# etherbotix.net
KiCad netlist of a schematic drawn in EAGLE
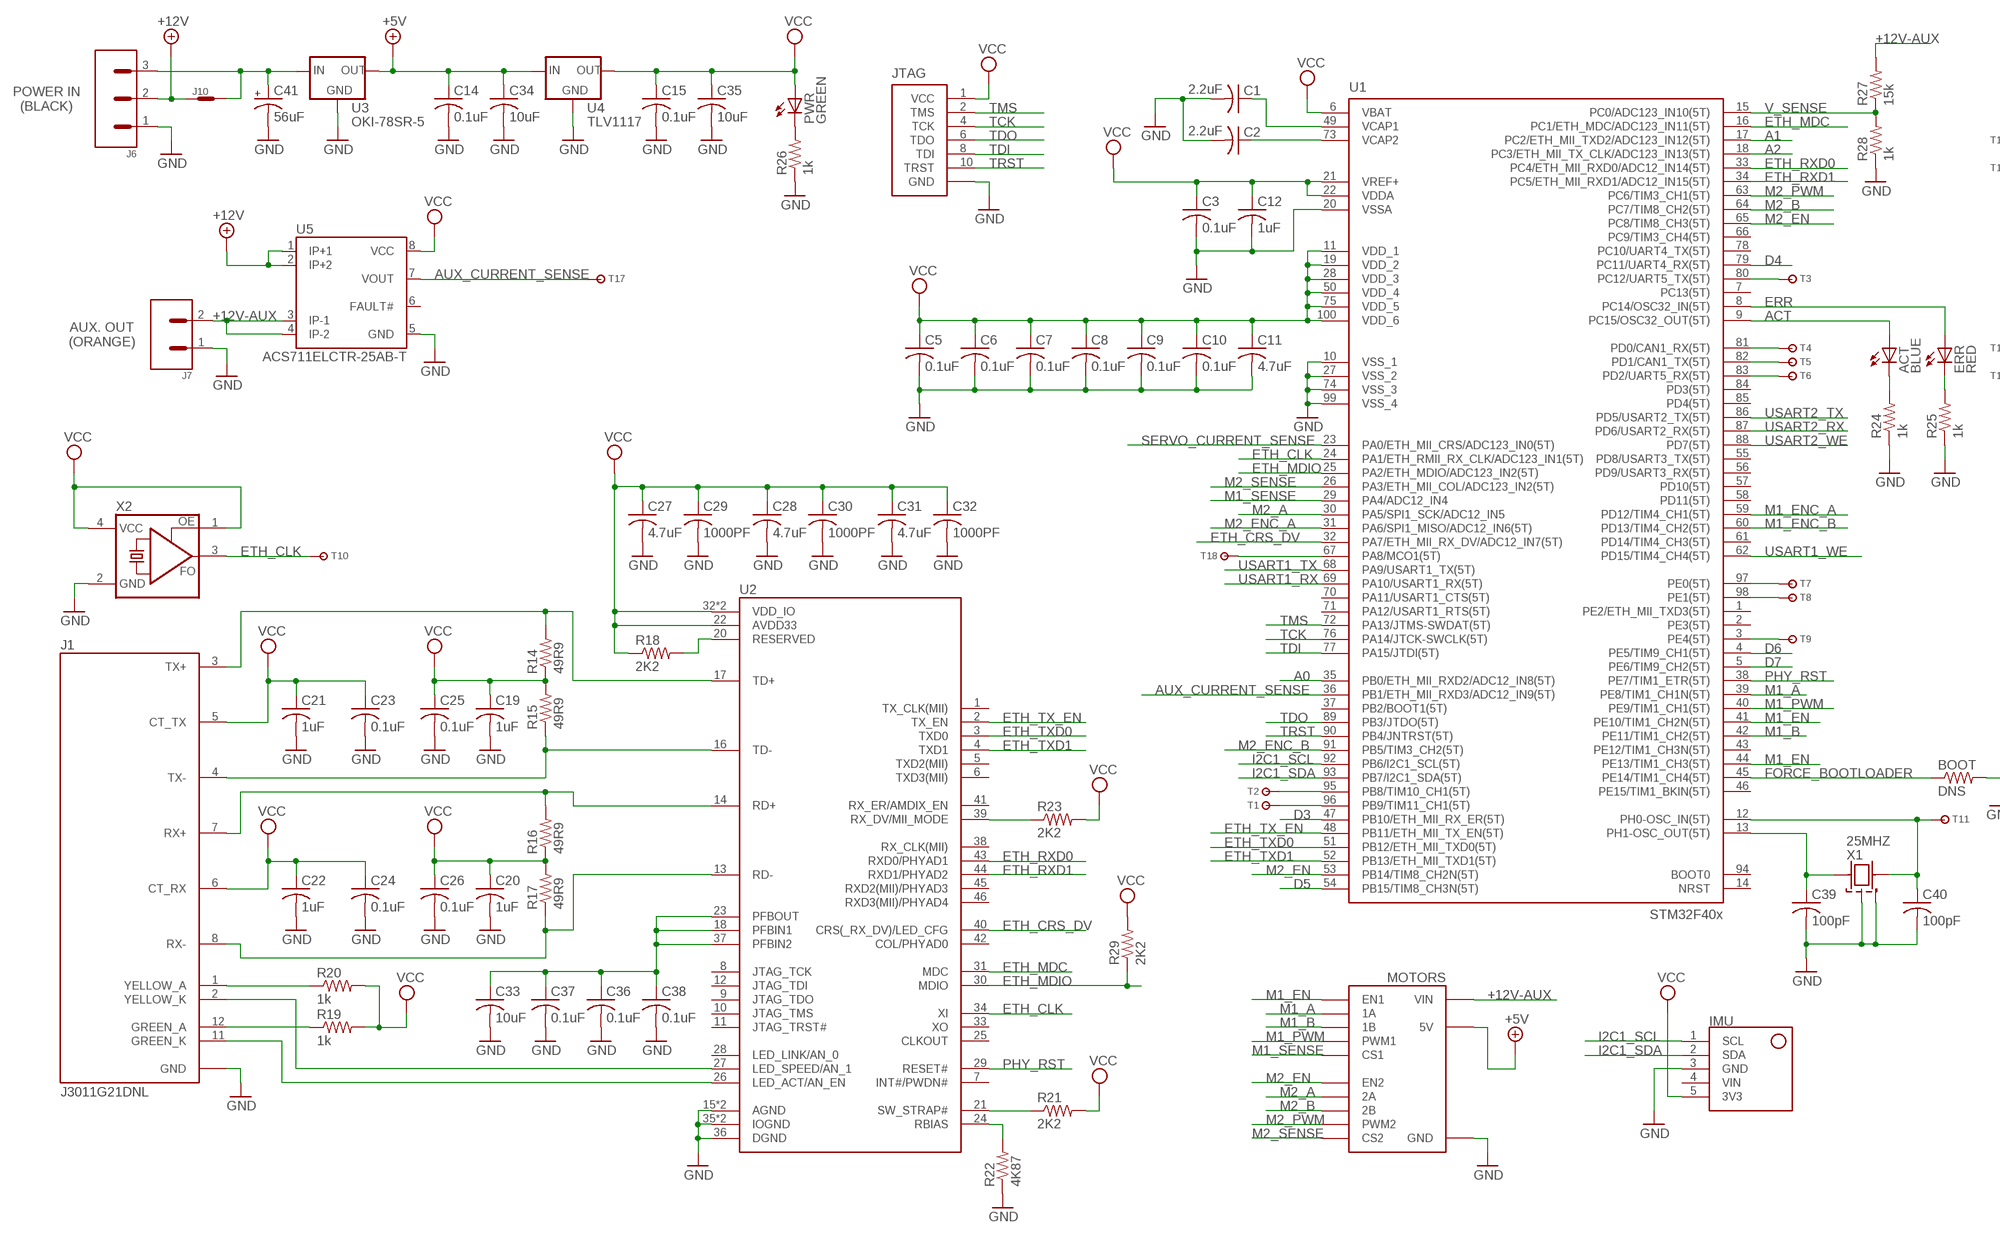
[diagram p0: schematic, sheet 1, part 1 of 2]
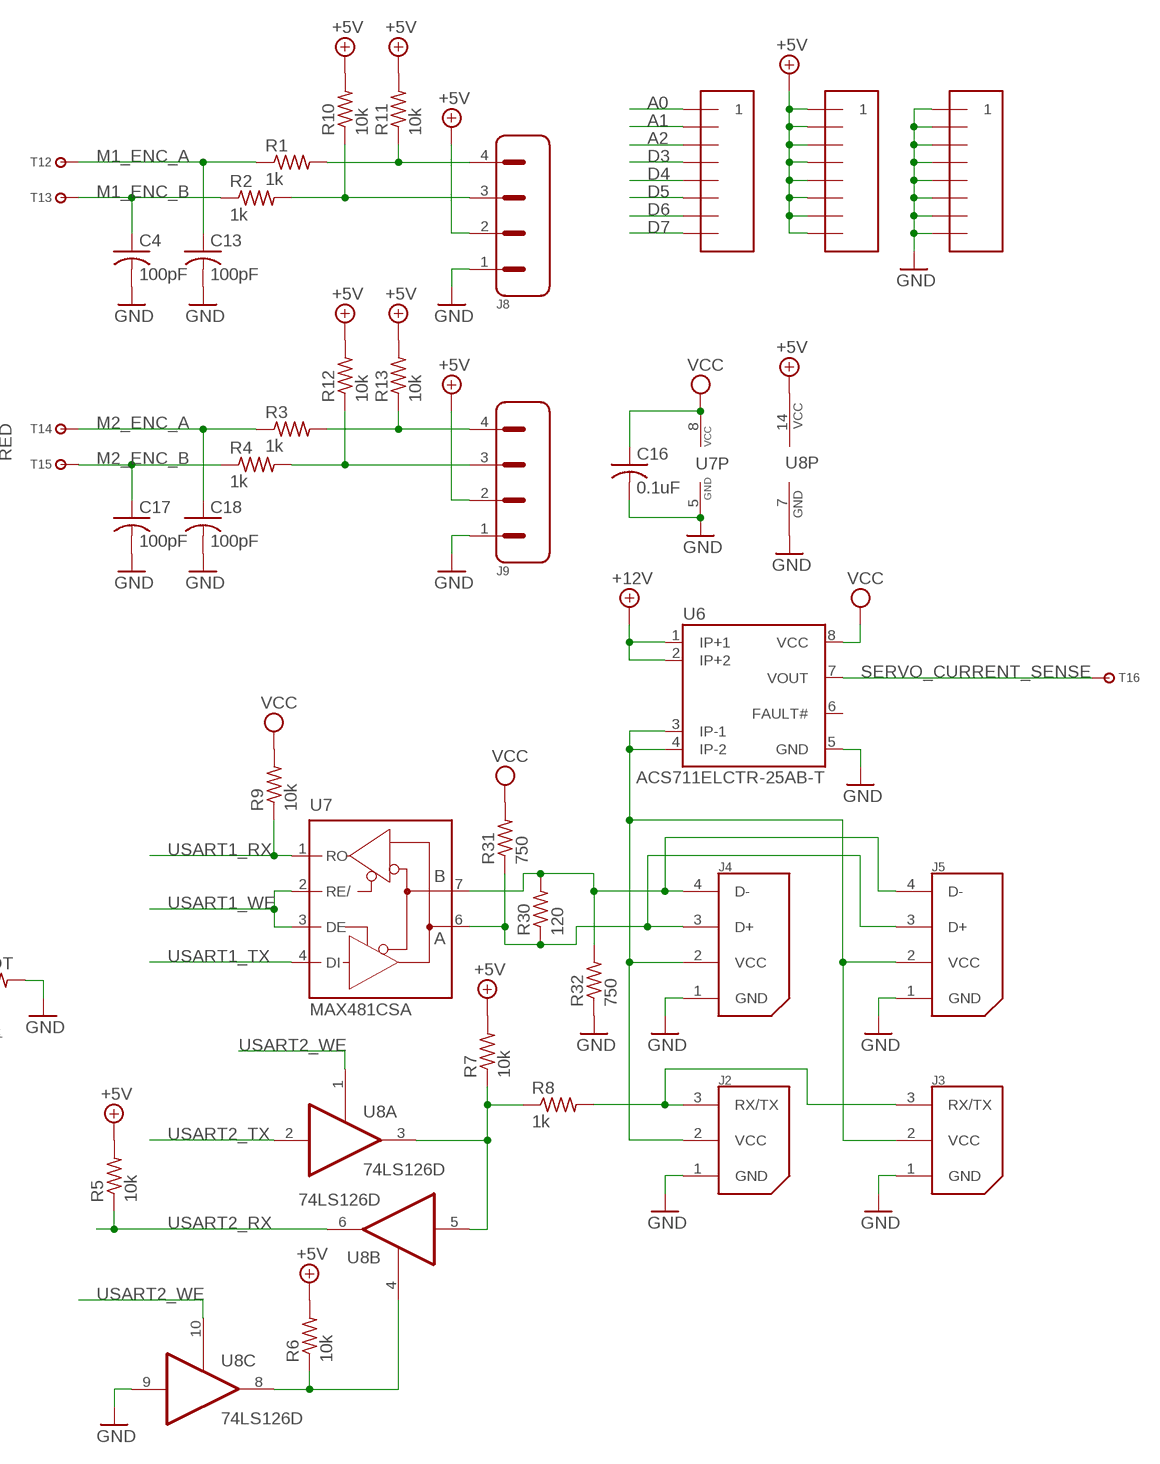
[diagram p1: schematic, sheet 1, part 2 of 2]

(export (version "E")
  (design (tool "Eeschema 10.0.6"))
  (components
    (comp (ref "ACT")
      (value "BLUE")
      (footprint "eagle-import:LED0603")
      (libsource (lib "eagle-import") (part "APT1608SGC"))
    )
    (comp (ref "BOOT")
      (value "DNS")
      (footprint "eagle-import:0603")
      (libsource (lib "eagle-import") (part "P1.00KHCT-ND"))
    )
    (comp (ref "C1")
      (value "2.2uF")
      (footprint "eagle-import:C0603")
      (libsource (lib "eagle-import") (part "C1608X5R1C225K"))
    )
    (comp (ref "C2")
      (value "2.2uF")
      (footprint "eagle-import:C0603")
      (libsource (lib "eagle-import") (part "C1608X5R1C225K"))
    )
    (comp (ref "C3")
      (value "0.1uF")
      (footprint "eagle-import:C0603")
      (libsource (lib "eagle-import") (part "C1608X7R1H104K"))
    )
    (comp (ref "C4")
      (value "100pF")
      (footprint "eagle-import:C0603")
      (libsource (lib "eagle-import") (part "C1608C0G1H101J"))
    )
    (comp (ref "C5")
      (value "0.1uF")
      (footprint "eagle-import:C0603")
      (libsource (lib "eagle-import") (part "C1608X7R1H104K"))
    )
    (comp (ref "C6")
      (value "0.1uF")
      (footprint "eagle-import:C0603")
      (libsource (lib "eagle-import") (part "C1608X7R1H104K"))
    )
    (comp (ref "C7")
      (value "0.1uF")
      (footprint "eagle-import:C0603")
      (libsource (lib "eagle-import") (part "C1608X7R1H104K"))
    )
    (comp (ref "C8")
      (value "0.1uF")
      (footprint "eagle-import:C0603")
      (libsource (lib "eagle-import") (part "C1608X7R1H104K"))
    )
    (comp (ref "C9")
      (value "0.1uF")
      (footprint "eagle-import:C0603")
      (libsource (lib "eagle-import") (part "C1608X7R1H104K"))
    )
    (comp (ref "C10")
      (value "0.1uF")
      (footprint "eagle-import:C0603")
      (libsource (lib "eagle-import") (part "C1608X7R1H104K"))
    )
    (comp (ref "C11")
      (value "4.7uF")
      (footprint "eagle-import:0603")
      (libsource (lib "eagle-import") (part "C1608X5R0J475K"))
    )
    (comp (ref "C12")
      (value "1uF")
      (footprint "eagle-import:C0603")
      (libsource (lib "eagle-import") (part "C1608X5R1H105M"))
    )
    (comp (ref "C13")
      (value "100pF")
      (footprint "eagle-import:C0603")
      (libsource (lib "eagle-import") (part "C1608C0G1H101J"))
    )
    (comp (ref "C14")
      (value "0.1uF")
      (footprint "eagle-import:C0603")
      (libsource (lib "eagle-import") (part "C1608X7R1H104K"))
    )
    (comp (ref "C15")
      (value "0.1uF")
      (footprint "eagle-import:C0603")
      (libsource (lib "eagle-import") (part "C1608X7R1H104K"))
    )
    (comp (ref "C16")
      (value "0.1uF")
      (footprint "eagle-import:C0603")
      (libsource (lib "eagle-import") (part "C1608X7R1H104K"))
    )
    (comp (ref "C17")
      (value "100pF")
      (footprint "eagle-import:C0603")
      (libsource (lib "eagle-import") (part "C1608C0G1H101J"))
    )
    (comp (ref "C18")
      (value "100pF")
      (footprint "eagle-import:C0603")
      (libsource (lib "eagle-import") (part "C1608C0G1H101J"))
    )
    (comp (ref "C19")
      (value "1uF")
      (footprint "eagle-import:C0603")
      (libsource (lib "eagle-import") (part "C1608X5R1H105M"))
    )
    (comp (ref "C20")
      (value "1uF")
      (footprint "eagle-import:C0603")
      (libsource (lib "eagle-import") (part "C1608X5R1H105M"))
    )
    (comp (ref "C21")
      (value "1uF")
      (footprint "eagle-import:C0603")
      (libsource (lib "eagle-import") (part "C1608X5R1H105M"))
    )
    (comp (ref "C22")
      (value "1uF")
      (footprint "eagle-import:C0603")
      (libsource (lib "eagle-import") (part "C1608X5R1H105M"))
    )
    (comp (ref "C23")
      (value "0.1uF")
      (footprint "eagle-import:C0603")
      (libsource (lib "eagle-import") (part "C1608X7R1H104K"))
    )
    (comp (ref "C24")
      (value "0.1uF")
      (footprint "eagle-import:C0603")
      (libsource (lib "eagle-import") (part "C1608X7R1H104K"))
    )
    (comp (ref "C25")
      (value "0.1uF")
      (footprint "eagle-import:C0603")
      (libsource (lib "eagle-import") (part "C1608X7R1H104K"))
    )
    (comp (ref "C26")
      (value "0.1uF")
      (footprint "eagle-import:C0603")
      (libsource (lib "eagle-import") (part "C1608X7R1H104K"))
    )
    (comp (ref "C27")
      (value "4.7uF")
      (footprint "eagle-import:0603")
      (libsource (lib "eagle-import") (part "C1608X5R0J475K"))
    )
    (comp (ref "C28")
      (value "4.7uF")
      (footprint "eagle-import:0603")
      (libsource (lib "eagle-import") (part "C1608X5R0J475K"))
    )
    (comp (ref "C29")
      (value "1000PF")
      (footprint "eagle-import:0603")
      (libsource (lib "eagle-import") (part "C1608X7R1H102K"))
    )
    (comp (ref "C30")
      (value "1000PF")
      (footprint "eagle-import:0603")
      (libsource (lib "eagle-import") (part "C1608X7R1H102K"))
    )
    (comp (ref "C31")
      (value "4.7uF")
      (footprint "eagle-import:0603")
      (libsource (lib "eagle-import") (part "C1608X5R0J475K"))
    )
    (comp (ref "C32")
      (value "1000PF")
      (footprint "eagle-import:0603")
      (libsource (lib "eagle-import") (part "C1608X7R1H102K"))
    )
    (comp (ref "C33")
      (value "10uF")
      (footprint "eagle-import:C0603")
      (libsource (lib "eagle-import") (part "C1608X5R0J106M"))
    )
    (comp (ref "C34")
      (value "10uF")
      (footprint "eagle-import:C0603")
      (libsource (lib "eagle-import") (part "C1608X5R0J106M"))
    )
    (comp (ref "C35")
      (value "10uF")
      (footprint "eagle-import:C0603")
      (libsource (lib "eagle-import") (part "C1608X5R0J106M"))
    )
    (comp (ref "C36")
      (value "0.1uF")
      (footprint "eagle-import:C0603")
      (libsource (lib "eagle-import") (part "C1608X7R1H104K"))
    )
    (comp (ref "C37")
      (value "0.1uF")
      (footprint "eagle-import:C0603")
      (libsource (lib "eagle-import") (part "C1608X7R1H104K"))
    )
    (comp (ref "C38")
      (value "0.1uF")
      (footprint "eagle-import:C0603")
      (libsource (lib "eagle-import") (part "C1608X7R1H104K"))
    )
    (comp (ref "C39")
      (value "100pF")
      (footprint "eagle-import:C0603")
      (libsource (lib "eagle-import") (part "C1608C0G1H101J"))
    )
    (comp (ref "C40")
      (value "100pF")
      (footprint "eagle-import:C0603")
      (libsource (lib "eagle-import") (part "C1608C0G1H101J"))
    )
    (comp (ref "C41")
      (value "56uF")
      (footprint "eagle-import:OSCON_SVPF_6.3MM")
      (libsource (lib "eagle-import") (part "25SVPF56M"))
    )
    (comp (ref "ERR")
      (value "RED")
      (footprint "eagle-import:LED0603")
      (libsource (lib "eagle-import") (part "APT1608SGC"))
    )
    (comp (ref "IMU")
      (value "MINI9IMU")
      (footprint "eagle-import:MINI9IMU")
      (libsource (lib "eagle-import") (part "MINI9IMU"))
    )
    (comp (ref "J1")
      (value "J3011G21DNL")
      (footprint "eagle-import:J3")
      (libsource (lib "eagle-import") (part "J3011G21DNL"))
    )
    (comp (ref "J2")
      (value "22-03-5035")
      (footprint "eagle-import:5267-3")
      (libsource (lib "eagle-import") (part "22-03-5035"))
    )
    (comp (ref "J3")
      (value "22-03-5035")
      (footprint "eagle-import:5267-3")
      (libsource (lib "eagle-import") (part "22-03-5035"))
    )
    (comp (ref "J4")
      (value "22-03-5045")
      (footprint "eagle-import:5267-4")
      (libsource (lib "eagle-import") (part "22-03-5045"))
    )
    (comp (ref "J5")
      (value "22-03-5045")
      (footprint "eagle-import:5267-4")
      (libsource (lib "eagle-import") (part "22-03-5045"))
    )
    (comp (ref "J6")
      (value "1760520000")
      (footprint "eagle-import:1760520000")
      (libsource (lib "eagle-import") (part "1760520000"))
    )
    (comp (ref "J7")
      (value "1760490000")
      (footprint "eagle-import:1760490000")
      (libsource (lib "eagle-import") (part "1760490000"))
    )
    (comp (ref "J8")
      (value "502443-0470")
      (footprint "eagle-import:502443-0470")
      (libsource (lib "eagle-import") (part "502443-0470"))
    )
    (comp (ref "J9")
      (value "502443-0470")
      (footprint "eagle-import:502443-0470")
      (libsource (lib "eagle-import") (part "502443-0470"))
    )
    (comp (ref "J10")
      (value "JUMPER")
      (footprint "eagle-import:J2")
      (libsource (lib "eagle-import") (part "JUMPER"))
    )
    (comp (ref "JTAG")
      (value "CORTEX_DEBUG-SHROUDED")
      (footprint "eagle-import:3220-10-0300-00")
      (libsource (lib "eagle-import") (part "CORTEX_DEBUG-SHROUDED"))
    )
    (comp (ref "MOTORS")
      (value "MD03A")
      (footprint "eagle-import:MD03A")
      (libsource (lib "eagle-import") (part "MD03A"))
    )
    (comp (ref "PWR")
      (value "GREEN")
      (footprint "eagle-import:LED0603")
      (libsource (lib "eagle-import") (part "APT1608SGC"))
    )
    (comp (ref "R1")
      (value "1k")
      (footprint "eagle-import:0603")
      (libsource (lib "eagle-import") (part "P1.00KHCT-ND"))
    )
    (comp (ref "R2")
      (value "1k")
      (footprint "eagle-import:0603")
      (libsource (lib "eagle-import") (part "P1.00KHCT-ND"))
    )
    (comp (ref "R3")
      (value "1k")
      (footprint "eagle-import:0603")
      (libsource (lib "eagle-import") (part "P1.00KHCT-ND"))
    )
    (comp (ref "R4")
      (value "1k")
      (footprint "eagle-import:0603")
      (libsource (lib "eagle-import") (part "P1.00KHCT-ND"))
    )
    (comp (ref "R5")
      (value "10k")
      (footprint "eagle-import:0603")
      (libsource (lib "eagle-import") (part "P10.0KHCT-ND"))
    )
    (comp (ref "R6")
      (value "10k")
      (footprint "eagle-import:0603")
      (libsource (lib "eagle-import") (part "P10.0KHCT-ND"))
    )
    (comp (ref "R7")
      (value "10k")
      (footprint "eagle-import:0603")
      (libsource (lib "eagle-import") (part "P10.0KHCT-ND"))
    )
    (comp (ref "R8")
      (value "1k")
      (footprint "eagle-import:0603")
      (libsource (lib "eagle-import") (part "P1.00KHCT-ND"))
    )
    (comp (ref "R9")
      (value "10k")
      (footprint "eagle-import:0603")
      (libsource (lib "eagle-import") (part "P10.0KHCT-ND"))
    )
    (comp (ref "R10")
      (value "10k")
      (footprint "eagle-import:0603")
      (libsource (lib "eagle-import") (part "P10.0KHCT-ND"))
    )
    (comp (ref "R11")
      (value "10k")
      (footprint "eagle-import:0603")
      (libsource (lib "eagle-import") (part "P10.0KHCT-ND"))
    )
    (comp (ref "R12")
      (value "10k")
      (footprint "eagle-import:0603")
      (libsource (lib "eagle-import") (part "P10.0KHCT-ND"))
    )
    (comp (ref "R13")
      (value "10k")
      (footprint "eagle-import:0603")
      (libsource (lib "eagle-import") (part "P10.0KHCT-ND"))
    )
    (comp (ref "R14")
      (value "49R9")
      (footprint "eagle-import:0603")
      (libsource (lib "eagle-import") (part "P49.9HCT-ND"))
    )
    (comp (ref "R15")
      (value "49R9")
      (footprint "eagle-import:0603")
      (libsource (lib "eagle-import") (part "P49.9HCT-ND"))
    )
    (comp (ref "R16")
      (value "49R9")
      (footprint "eagle-import:0603")
      (libsource (lib "eagle-import") (part "P49.9HCT-ND"))
    )
    (comp (ref "R17")
      (value "49R9")
      (footprint "eagle-import:0603")
      (libsource (lib "eagle-import") (part "P49.9HCT-ND"))
    )
    (comp (ref "R18")
      (value "2K2")
      (footprint "eagle-import:0603")
      (libsource (lib "eagle-import") (part "P2.20KHCT-ND"))
    )
    (comp (ref "R19")
      (value "1k")
      (footprint "eagle-import:0603")
      (libsource (lib "eagle-import") (part "P1.00KHCT-ND"))
    )
    (comp (ref "R20")
      (value "1k")
      (footprint "eagle-import:0603")
      (libsource (lib "eagle-import") (part "P1.00KHCT-ND"))
    )
    (comp (ref "R21")
      (value "2K2")
      (footprint "eagle-import:0603")
      (libsource (lib "eagle-import") (part "P2.20KHCT-ND"))
    )
    (comp (ref "R22")
      (value "4K87")
      (footprint "eagle-import:0603")
      (libsource (lib "eagle-import") (part "P4.87KHCT-ND"))
    )
    (comp (ref "R23")
      (value "2K2")
      (footprint "eagle-import:0603")
      (libsource (lib "eagle-import") (part "P2.20KHCT-ND"))
    )
    (comp (ref "R24")
      (value "1k")
      (footprint "eagle-import:0603")
      (libsource (lib "eagle-import") (part "P1.00KHCT-ND"))
    )
    (comp (ref "R25")
      (value "1k")
      (footprint "eagle-import:0603")
      (libsource (lib "eagle-import") (part "P1.00KHCT-ND"))
    )
    (comp (ref "R26")
      (value "1k")
      (footprint "eagle-import:0603")
      (libsource (lib "eagle-import") (part "P1.00KHCT-ND"))
    )
    (comp (ref "R27")
      (value "15k")
      (footprint "eagle-import:0603")
      (libsource (lib "eagle-import") (part "P15.0KHCT-ND"))
    )
    (comp (ref "R28")
      (value "1k")
      (footprint "eagle-import:0603")
      (libsource (lib "eagle-import") (part "P1.00KHCT-ND"))
    )
    (comp (ref "R29")
      (value "2K2")
      (footprint "eagle-import:0603")
      (libsource (lib "eagle-import") (part "P2.20KHCT-ND"))
    )
    (comp (ref "R30")
      (value "120")
      (footprint "eagle-import:0603")
      (libsource (lib "eagle-import") (part "P120HCT-ND"))
    )
    (comp (ref "R31")
      (value "750")
      (footprint "eagle-import:0603")
      (libsource (lib "eagle-import") (part "P750HCT-ND"))
    )
    (comp (ref "R32")
      (value "750")
      (footprint "eagle-import:0603")
      (libsource (lib "eagle-import") (part "P750HCT-ND"))
    )
    (comp (ref "T1")
      (value "TESTPAD")
      (footprint "eagle-import:TEST")
      (libsource (lib "eagle-import") (part "TESTPAD"))
    )
    (comp (ref "T2")
      (value "TESTPAD")
      (footprint "eagle-import:TEST")
      (libsource (lib "eagle-import") (part "TESTPAD"))
    )
    (comp (ref "T3")
      (value "TESTPAD")
      (footprint "eagle-import:TEST")
      (libsource (lib "eagle-import") (part "TESTPAD"))
    )
    (comp (ref "T4")
      (value "TESTPAD")
      (footprint "eagle-import:TEST")
      (libsource (lib "eagle-import") (part "TESTPAD"))
    )
    (comp (ref "T5")
      (value "TESTPAD")
      (footprint "eagle-import:TEST")
      (libsource (lib "eagle-import") (part "TESTPAD"))
    )
    (comp (ref "T6")
      (value "TESTPAD")
      (footprint "eagle-import:TEST")
      (libsource (lib "eagle-import") (part "TESTPAD"))
    )
    (comp (ref "T7")
      (value "TESTPAD")
      (footprint "eagle-import:TEST")
      (libsource (lib "eagle-import") (part "TESTPAD"))
    )
    (comp (ref "T8")
      (value "TESTPAD")
      (footprint "eagle-import:TEST")
      (libsource (lib "eagle-import") (part "TESTPAD"))
    )
    (comp (ref "T9")
      (value "TESTPAD")
      (footprint "eagle-import:TEST")
      (libsource (lib "eagle-import") (part "TESTPAD"))
    )
    (comp (ref "T10")
      (value "TESTPAD")
      (footprint "eagle-import:TEST")
      (libsource (lib "eagle-import") (part "TESTPAD"))
    )
    (comp (ref "T11")
      (value "TESTPAD")
      (footprint "eagle-import:TEST")
      (libsource (lib "eagle-import") (part "TESTPAD"))
    )
    (comp (ref "T12")
      (value "TESTPAD")
      (footprint "eagle-import:TEST")
      (libsource (lib "eagle-import") (part "TESTPAD"))
    )
    (comp (ref "T13")
      (value "TESTPAD")
      (footprint "eagle-import:TEST")
      (libsource (lib "eagle-import") (part "TESTPAD"))
    )
    (comp (ref "T14")
      (value "TESTPAD")
      (footprint "eagle-import:TEST")
      (libsource (lib "eagle-import") (part "TESTPAD"))
    )
    (comp (ref "T15")
      (value "TESTPAD")
      (footprint "eagle-import:TEST")
      (libsource (lib "eagle-import") (part "TESTPAD"))
    )
    (comp (ref "T16")
      (value "TESTPAD")
      (footprint "eagle-import:TEST")
      (libsource (lib "eagle-import") (part "TESTPAD"))
    )
    (comp (ref "T17")
      (value "TESTPAD")
      (footprint "eagle-import:TEST")
      (libsource (lib "eagle-import") (part "TESTPAD"))
    )
    (comp (ref "T18")
      (value "TESTPAD")
      (footprint "eagle-import:TEST")
      (libsource (lib "eagle-import") (part "TESTPAD"))
    )
    (comp (ref "U$1")
      (value "HEADER8")
      (footprint "eagle-import:1X8")
      (libsource (lib "eagle-import") (part "HEADER8"))
    )
    (comp (ref "U$2")
      (value "HEADER8")
      (footprint "eagle-import:1X8")
      (libsource (lib "eagle-import") (part "HEADER8"))
    )
    (comp (ref "U$3")
      (value "HEADER8")
      (footprint "eagle-import:1X8")
      (libsource (lib "eagle-import") (part "HEADER8"))
    )
    (comp (ref "U1")
      (value "STM32F407V")
      (footprint "eagle-import:TQFP100")
      (libsource (lib "eagle-import") (part "STM32F407V"))
    )
    (comp (ref "U2")
      (value "TLK110")
      (footprint "eagle-import:LQFP48")
      (libsource (lib "eagle-import") (part "TLK110"))
    )
    (comp (ref "U3")
      (value "OKI-78SR-5")
      (footprint "eagle-import:OKI-78SR")
      (fields (field (name "VOLTAGE") "5"))
      (libsource (lib "eagle-import") (part "OKI-78SR-W36-C-5/1.5"))
    )
    (comp (ref "U4")
      (value "TLV1117")
      (footprint "eagle-import:DPAK")
      (libsource (lib "eagle-import") (part "TLV1117-33IKVURG3KVU"))
    )
    (comp (ref "U5")
      (value "ACS711ELCTR-25AB-T")
      (footprint "eagle-import:SOIC8")
      (libsource (lib "eagle-import") (part "ACS711ELC?TR-25AB-T"))
    )
    (comp (ref "U6")
      (value "ACS711ELCTR-25AB-T")
      (footprint "eagle-import:SOIC8")
      (libsource (lib "eagle-import") (part "ACS711ELC?TR-25AB-T"))
    )
    (comp (ref "U7")
      (value "MAX481CSA")
      (footprint "eagle-import:SO08")
      (fields (field (name "MF") "MAXIM"))
      (libsource (lib "eagle-import") (part "MAX481CSA"))
    )
    (comp (ref "U8")
      (value "74LS126D")
      (footprint "eagle-import:SO14")
      (libsource (lib "eagle-import") (part "74126DLS"))
    )
    (comp (ref "X1")
      (value "25MHZ")
      (footprint "eagle-import:4LCC")
      (libsource (lib "eagle-import") (part "ABM3B-MHZ-B2-T25.000"))
    )
    (comp (ref "X2")
      (value "ASEMB-50.000MHZ-XY-T")
      (footprint "eagle-import:OSCILLATOR")
      (libsource (lib "eagle-import") (part "ASEMB-50.000MHZ-XY-T"))
    )
  )
  (nets
    (net (code "1") (name "+5V") (class "Default")
      (node (ref "C14") (pin "1") (pinfunction "1_1") (pintype "passive"))
      (node (ref "C34") (pin "1") (pinfunction "1_1") (pintype "passive"))
      (node (ref "J8") (pin "2") (pinfunction "2_2") (pintype "bidirectional"))
      (node (ref "J9") (pin "2") (pinfunction "2_2") (pintype "bidirectional"))
      (node (ref "MOTORS") (pin "5V") (pinfunction "5V_5V") (pintype "bidirectional"))
      (node (ref "R10") (pin "2") (pinfunction "2_2") (pintype "passive"))
      (node (ref "R11") (pin "2") (pinfunction "2_2") (pintype "passive"))
      (node (ref "R12") (pin "2") (pinfunction "2_2") (pintype "passive"))
      (node (ref "R13") (pin "2") (pinfunction "2_2") (pintype "passive"))
      (node (ref "R5") (pin "2") (pinfunction "2_2") (pintype "passive"))
      (node (ref "R6") (pin "2") (pinfunction "2_2") (pintype "passive"))
      (node (ref "R7") (pin "2") (pinfunction "2_2") (pintype "passive"))
      (node (ref "U$2") (pin "P$1") (pinfunction "1_P$1") (pintype "bidirectional"))
      (node (ref "U$2") (pin "P$2") (pinfunction "P$2_P$2") (pintype "bidirectional"))
      (node (ref "U$2") (pin "P$3") (pinfunction "P$3_P$3") (pintype "bidirectional"))
      (node (ref "U$2") (pin "P$4") (pinfunction "P$4_P$4") (pintype "bidirectional"))
      (node (ref "U$2") (pin "P$5") (pinfunction "P$5_P$5") (pintype "bidirectional"))
      (node (ref "U$2") (pin "P$6") (pinfunction "P$6_P$6") (pintype "bidirectional"))
      (node (ref "U$2") (pin "P$7") (pinfunction "P$7_P$7") (pintype "bidirectional"))
      (node (ref "U$2") (pin "P$8") (pinfunction "P$8_P$8") (pintype "bidirectional"))
      (node (ref "U3") (pin "P$3") (pinfunction "OUT_P$3") (pintype "passive"))
      (node (ref "U4") (pin "3") (pinfunction "IN_3") (pintype "input"))
      (node (ref "U8") (pin "14") (pinfunction "VCC_14") (pintype "power_in"))
    )
    (net (code "2") (name "+12V") (class "Default")
      (node (ref "J10") (pin "A") (pinfunction "A_A") (pintype "bidirectional"))
      (node (ref "J6") (pin "2") (pinfunction "2_2") (pintype "bidirectional"))
      (node (ref "U5") (pin "1") (pinfunction "IP+1_1") (pintype "bidirectional"))
      (node (ref "U5") (pin "2") (pinfunction "IP+2_2") (pintype "bidirectional"))
      (node (ref "U6") (pin "1") (pinfunction "IP+1_1") (pintype "bidirectional"))
      (node (ref "U6") (pin "2") (pinfunction "IP+2_2") (pintype "bidirectional"))
    )
    (net (code "3") (name "/+12V-AUX") (class "Default")
      (node (ref "J7") (pin "2") (pinfunction "2_2") (pintype "bidirectional"))
      (node (ref "MOTORS") (pin "VIN1") (pinfunction "VIN_VIN1") (pintype "bidirectional"))
      (node (ref "MOTORS") (pin "VIN2") (pinfunction "VIN_VIN2") (pintype "bidirectional"))
      (node (ref "R27") (pin "2") (pinfunction "2_2") (pintype "passive"))
      (node (ref "U5") (pin "3") (pinfunction "IP-1_3") (pintype "bidirectional"))
      (node (ref "U5") (pin "4") (pinfunction "IP-2_4") (pintype "bidirectional"))
    )
    (net (code "4") (name "/A0") (class "Default")
      (node (ref "U$1") (pin "P$1") (pinfunction "1_P$1") (pintype "bidirectional"))
      (node (ref "U1") (pin "35") (pinfunction "PB0/ETH_MII_RXD2/ADC12_IN8(5T)_35") (pintype "bidirectional"))
    )
    (net (code "5") (name "/A1") (class "Default")
      (node (ref "U$1") (pin "P$2") (pinfunction "P$2_P$2") (pintype "bidirectional"))
      (node (ref "U1") (pin "17") (pinfunction "PC2/ETH_MII_TXD2/ADC123_IN12(5T)_17") (pintype "bidirectional"))
    )
    (net (code "6") (name "/A2") (class "Default")
      (node (ref "U$1") (pin "P$3") (pinfunction "P$3_P$3") (pintype "bidirectional"))
      (node (ref "U1") (pin "18") (pinfunction "PC3/ETH_MII_TX_CLK/ADC123_IN13(5T)_18") (pintype "bidirectional"))
    )
    (net (code "7") (name "/ACT") (class "Default")
      (node (ref "ACT") (pin "A") (pinfunction "A_A") (pintype "passive"))
      (node (ref "U1") (pin "9") (pinfunction "PC15/OSC32_OUT(5T)_9") (pintype "bidirectional"))
    )
    (net (code "8") (name "/AUX_CURRENT_SENSE") (class "Default")
      (node (ref "T17") (pin "T") (pinfunction "1_T") (pintype "bidirectional"))
      (node (ref "U1") (pin "36") (pinfunction "PB1/ETH_MII_RXD3/ADC12_IN9(5T)_36") (pintype "bidirectional"))
      (node (ref "U5") (pin "7") (pinfunction "VOUT_7") (pintype "bidirectional"))
    )
    (net (code "9") (name "/D3") (class "Default")
      (node (ref "U$1") (pin "P$4") (pinfunction "P$4_P$4") (pintype "bidirectional"))
      (node (ref "U1") (pin "47") (pinfunction "PB10/ETH_MII_RX_ER(5T)_47") (pintype "bidirectional"))
    )
    (net (code "10") (name "/D4") (class "Default")
      (node (ref "U$1") (pin "P$5") (pinfunction "P$5_P$5") (pintype "bidirectional"))
      (node (ref "U1") (pin "79") (pinfunction "PC11/UART4_RX(5T)_79") (pintype "bidirectional"))
    )
    (net (code "11") (name "/D5") (class "Default")
      (node (ref "U$1") (pin "P$6") (pinfunction "P$6_P$6") (pintype "bidirectional"))
      (node (ref "U1") (pin "54") (pinfunction "PB15/TIM8_CH3N(5T)_54") (pintype "bidirectional"))
    )
    (net (code "12") (name "/D6") (class "Default")
      (node (ref "U$1") (pin "P$7") (pinfunction "P$7_P$7") (pintype "bidirectional"))
      (node (ref "U1") (pin "4") (pinfunction "PE5/TIM9_CH1(5T)_4") (pintype "bidirectional"))
    )
    (net (code "13") (name "/D7") (class "Default")
      (node (ref "U$1") (pin "P$8") (pinfunction "P$8_P$8") (pintype "bidirectional"))
      (node (ref "U1") (pin "5") (pinfunction "PE6/TIM9_CH2(5T)_5") (pintype "bidirectional"))
    )
    (net (code "14") (name "/ERR") (class "Default")
      (node (ref "ERR") (pin "A") (pinfunction "A_A") (pintype "passive"))
      (node (ref "U1") (pin "8") (pinfunction "PC14/OSC32_IN(5T)_8") (pintype "bidirectional"))
    )
    (net (code "15") (name "/ETH_CLK") (class "Default")
      (node (ref "T10") (pin "T") (pinfunction "1_T") (pintype "bidirectional"))
      (node (ref "U1") (pin "24") (pinfunction "PA1/ETH_RMII_RX_CLK/ADC123_IN1(5T)_24") (pintype "bidirectional"))
      (node (ref "U2") (pin "34") (pinfunction "XI_34") (pintype "bidirectional"))
      (node (ref "X2") (pin "3") (pinfunction "FO_3") (pintype "output"))
    )
    (net (code "16") (name "/ETH_CRS_DV") (class "Default")
      (node (ref "U1") (pin "32") (pinfunction "PA7/ETH_MII_RX_DV/ADC12_IN7(5T)_32") (pintype "bidirectional"))
      (node (ref "U2") (pin "40") (pinfunction "CRS(_RX_DV)/LED_CFG_40") (pintype "bidirectional"))
    )
    (net (code "17") (name "/ETH_MDC") (class "Default")
      (node (ref "U1") (pin "16") (pinfunction "PC1/ETH_MDC/ADC123_IN11(5T)_16") (pintype "bidirectional"))
      (node (ref "U2") (pin "31") (pinfunction "MDC_31") (pintype "bidirectional"))
    )
    (net (code "18") (name "/ETH_MDIO") (class "Default")
      (node (ref "R29") (pin "1") (pinfunction "1_1") (pintype "passive"))
      (node (ref "U1") (pin "25") (pinfunction "PA2/ETH_MDIO/ADC123_IN2(5T)_25") (pintype "bidirectional"))
      (node (ref "U2") (pin "30") (pinfunction "MDIO_30") (pintype "bidirectional"))
    )
    (net (code "19") (name "/ETH_RXD0") (class "Default")
      (node (ref "U1") (pin "33") (pinfunction "PC4/ETH_MII_RXD0/ADC12_IN14(5T)_33") (pintype "bidirectional"))
      (node (ref "U2") (pin "43") (pinfunction "RXD0/PHYAD1_43") (pintype "bidirectional"))
    )
    (net (code "20") (name "/ETH_RXD1") (class "Default")
      (node (ref "U1") (pin "34") (pinfunction "PC5/ETH_MII_RXD1/ADC12_IN15(5T)_34") (pintype "bidirectional"))
      (node (ref "U2") (pin "44") (pinfunction "RXD1/PHYAD2_44") (pintype "bidirectional"))
    )
    (net (code "21") (name "/ETH_TXD0") (class "Default")
      (node (ref "U1") (pin "51") (pinfunction "PB12/ETH_MII_TXD0(5T)_51") (pintype "bidirectional"))
      (node (ref "U2") (pin "3") (pinfunction "TXD0_3") (pintype "bidirectional"))
    )
    (net (code "22") (name "/ETH_TXD1") (class "Default")
      (node (ref "U1") (pin "52") (pinfunction "PB13/ETH_MII_TXD1(5T)_52") (pintype "bidirectional"))
      (node (ref "U2") (pin "4") (pinfunction "TXD1_4") (pintype "bidirectional"))
    )
    (net (code "23") (name "/ETH_TX_EN") (class "Default")
      (node (ref "U1") (pin "48") (pinfunction "PB11/ETH_MII_TX_EN(5T)_48") (pintype "bidirectional"))
      (node (ref "U2") (pin "2") (pinfunction "TX_EN_2") (pintype "bidirectional"))
    )
    (net (code "24") (name "/FORCE_BOOTLOADER") (class "Default")
      (node (ref "BOOT") (pin "1") (pinfunction "1_1") (pintype "passive"))
      (node (ref "U1") (pin "45") (pinfunction "PE14/TIM1_CH4(5T)_45") (pintype "bidirectional"))
    )
    (net (code "25") (name "/I2C1_SCL") (class "Default")
      (node (ref "IMU") (pin "1") (pinfunction "SCL_1") (pintype "bidirectional"))
      (node (ref "U1") (pin "92") (pinfunction "PB6/I2C1_SCL(5T)_92") (pintype "bidirectional"))
    )
    (net (code "26") (name "/I2C1_SDA") (class "Default")
      (node (ref "IMU") (pin "2") (pinfunction "SDA_2") (pintype "bidirectional"))
      (node (ref "U1") (pin "93") (pinfunction "PB7/I2C1_SDA(5T)_93") (pintype "bidirectional"))
    )
    (net (code "27") (name "/M1_A") (class "Default")
      (node (ref "MOTORS") (pin "1A") (pinfunction "1A_1A") (pintype "bidirectional"))
      (node (ref "U1") (pin "39") (pinfunction "PE8/TIM1_CH1N(5T)_39") (pintype "bidirectional"))
    )
    (net (code "28") (name "/M1_B") (class "Default")
      (node (ref "MOTORS") (pin "1B") (pinfunction "1B_1B") (pintype "bidirectional"))
      (node (ref "U1") (pin "42") (pinfunction "PE11/TIM1_CH2(5T)_42") (pintype "bidirectional"))
    )
    (net (code "29") (name "/M1_EN") (class "Default")
      (node (ref "MOTORS") (pin "EN1") (pinfunction "EN1_EN1") (pintype "bidirectional"))
      (node (ref "U1") (pin "41") (pinfunction "PE10/TIM1_CH2N(5T)_41") (pintype "bidirectional"))
      (node (ref "U1") (pin "44") (pinfunction "PE13/TIM1_CH3(5T)_44") (pintype "bidirectional"))
    )
    (net (code "30") (name "/M1_ENC_A") (class "Default")
      (node (ref "C13") (pin "1") (pinfunction "1_1") (pintype "passive"))
      (node (ref "R1") (pin "1") (pinfunction "1_1") (pintype "passive"))
      (node (ref "T12") (pin "T") (pinfunction "1_T") (pintype "bidirectional"))
      (node (ref "U1") (pin "59") (pinfunction "PD12/TIM4_CH1(5T)_59") (pintype "bidirectional"))
    )
    (net (code "31") (name "/M1_ENC_B") (class "Default")
      (node (ref "C4") (pin "1") (pinfunction "1_1") (pintype "passive"))
      (node (ref "R2") (pin "1") (pinfunction "1_1") (pintype "passive"))
      (node (ref "T13") (pin "T") (pinfunction "1_T") (pintype "bidirectional"))
      (node (ref "U1") (pin "60") (pinfunction "PD13/TIM4_CH2(5T)_60") (pintype "bidirectional"))
    )
    (net (code "32") (name "/M1_PWM") (class "Default")
      (node (ref "MOTORS") (pin "PWM1") (pinfunction "PWM1_PWM1") (pintype "bidirectional"))
      (node (ref "U1") (pin "40") (pinfunction "PE9/TIM1_CH1(5T)_40") (pintype "bidirectional"))
    )
    (net (code "33") (name "/M1_SENSE") (class "Default")
      (node (ref "MOTORS") (pin "CS1") (pinfunction "CS1_CS1") (pintype "bidirectional"))
      (node (ref "U1") (pin "29") (pinfunction "PA4/ADC12_IN4_29") (pintype "bidirectional"))
    )
    (net (code "34") (name "/M2_A") (class "Default")
      (node (ref "MOTORS") (pin "2A") (pinfunction "2A_2A") (pintype "bidirectional"))
      (node (ref "U1") (pin "30") (pinfunction "PA5/SPI1_SCK/ADC12_IN5_30") (pintype "bidirectional"))
    )
    (net (code "35") (name "/M2_B") (class "Default")
      (node (ref "MOTORS") (pin "2B") (pinfunction "2B_2B") (pintype "bidirectional"))
      (node (ref "U1") (pin "64") (pinfunction "PC7/TIM8_CH2(5T)_64") (pintype "bidirectional"))
    )
    (net (code "36") (name "/M2_EN") (class "Default")
      (node (ref "MOTORS") (pin "EN2") (pinfunction "EN2_EN2") (pintype "bidirectional"))
      (node (ref "U1") (pin "53") (pinfunction "PB14/TIM8_CH2N(5T)_53") (pintype "bidirectional"))
      (node (ref "U1") (pin "65") (pinfunction "PC8/TIM8_CH3(5T)_65") (pintype "bidirectional"))
    )
    (net (code "37") (name "/M2_ENC_A") (class "Default")
      (node (ref "C18") (pin "1") (pinfunction "1_1") (pintype "passive"))
      (node (ref "R3") (pin "1") (pinfunction "1_1") (pintype "passive"))
      (node (ref "T14") (pin "T") (pinfunction "1_T") (pintype "bidirectional"))
      (node (ref "U1") (pin "31") (pinfunction "PA6/SPI1_MISO/ADC12_IN6(5T)_31") (pintype "bidirectional"))
    )
    (net (code "38") (name "/M2_ENC_B") (class "Default")
      (node (ref "C17") (pin "1") (pinfunction "1_1") (pintype "passive"))
      (node (ref "R4") (pin "1") (pinfunction "1_1") (pintype "passive"))
      (node (ref "T15") (pin "T") (pinfunction "1_T") (pintype "bidirectional"))
      (node (ref "U1") (pin "91") (pinfunction "PB5/TIM3_CH2(5T)_91") (pintype "bidirectional"))
    )
    (net (code "39") (name "/M2_PWM") (class "Default")
      (node (ref "MOTORS") (pin "PWM2") (pinfunction "PWM2_PWM2") (pintype "bidirectional"))
      (node (ref "U1") (pin "63") (pinfunction "PC6/TIM3_CH1(5T)_63") (pintype "bidirectional"))
    )
    (net (code "40") (name "/M2_SENSE") (class "Default")
      (node (ref "MOTORS") (pin "CS2") (pinfunction "CS2_CS2") (pintype "bidirectional"))
      (node (ref "U1") (pin "26") (pinfunction "PA3/ETH_MII_COL/ADC123_IN2(5T)_26") (pintype "bidirectional"))
    )
    (net (code "41") (name "/PHY_RST") (class "Default")
      (node (ref "U1") (pin "38") (pinfunction "PE7/TIM1_ETR(5T)_38") (pintype "bidirectional"))
      (node (ref "U2") (pin "29") (pinfunction "RESET#_29") (pintype "bidirectional"))
    )
    (net (code "42") (name "/SERVO_CURRENT_SENSE") (class "Default")
      (node (ref "T16") (pin "T") (pinfunction "1_T") (pintype "bidirectional"))
      (node (ref "U1") (pin "23") (pinfunction "PA0/ETH_MII_CRS/ADC123_IN0(5T)_23") (pintype "bidirectional"))
      (node (ref "U6") (pin "7") (pinfunction "VOUT_7") (pintype "bidirectional"))
    )
    (net (code "43") (name "/TCK") (class "Default")
      (node (ref "JTAG") (pin "4") (pinfunction "TCK_4") (pintype "bidirectional"))
      (node (ref "U1") (pin "76") (pinfunction "PA14/JTCK-SWCLK(5T)_76") (pintype "bidirectional"))
    )
    (net (code "44") (name "/TDI") (class "Default")
      (node (ref "JTAG") (pin "8") (pinfunction "TDI_8") (pintype "bidirectional"))
      (node (ref "U1") (pin "77") (pinfunction "PA15/JTDI(5T)_77") (pintype "bidirectional"))
    )
    (net (code "45") (name "/TDO") (class "Default")
      (node (ref "JTAG") (pin "6") (pinfunction "TDO_6") (pintype "bidirectional"))
      (node (ref "U1") (pin "89") (pinfunction "PB3/JTDO(5T)_89") (pintype "bidirectional"))
    )
    (net (code "46") (name "/TMS") (class "Default")
      (node (ref "JTAG") (pin "2") (pinfunction "TMS_2") (pintype "bidirectional"))
      (node (ref "U1") (pin "72") (pinfunction "PA13/JTMS-SWDAT(5T)_72") (pintype "bidirectional"))
    )
    (net (code "47") (name "/TRST") (class "Default")
      (node (ref "JTAG") (pin "10") (pinfunction "TRST_10") (pintype "bidirectional"))
      (node (ref "U1") (pin "90") (pinfunction "PB4/JNTRST(5T)_90") (pintype "bidirectional"))
    )
    (net (code "48") (name "/USART1_RX") (class "Default")
      (node (ref "R9") (pin "1") (pinfunction "1_1") (pintype "passive"))
      (node (ref "U1") (pin "69") (pinfunction "PA10/USART1_RX(5T)_69") (pintype "bidirectional"))
      (node (ref "U7") (pin "1") (pinfunction "RO_1") (pintype "output"))
    )
    (net (code "49") (name "/USART1_TX") (class "Default")
      (node (ref "U1") (pin "68") (pinfunction "PA9/USART1_TX(5T)_68") (pintype "bidirectional"))
      (node (ref "U7") (pin "4") (pinfunction "DI_4") (pintype "input"))
    )
    (net (code "50") (name "/USART1_WE") (class "Default")
      (node (ref "U1") (pin "62") (pinfunction "PD15/TIM4_CH4(5T)_62") (pintype "bidirectional"))
      (node (ref "U7") (pin "2") (pinfunction "RE/_2") (pintype "input"))
      (node (ref "U7") (pin "3") (pinfunction "DE_3") (pintype "input"))
    )
    (net (code "51") (name "/USART2_RX") (class "Default")
      (node (ref "R5") (pin "1") (pinfunction "1_1") (pintype "passive"))
      (node (ref "U1") (pin "87") (pinfunction "PD6/USART2_RX(5T)_87") (pintype "bidirectional"))
      (node (ref "U8") (pin "6") (pinfunction "O_6") (pintype "output"))
    )
    (net (code "52") (name "/USART2_TX") (class "Default")
      (node (ref "U1") (pin "86") (pinfunction "PD5/USART2_TX(5T)_86") (pintype "bidirectional"))
      (node (ref "U8") (pin "2") (pinfunction "I_2") (pintype "input"))
    )
    (net (code "53") (name "/USART2_WE") (class "Default")
      (node (ref "U1") (pin "88") (pinfunction "PD7(5T)_88") (pintype "bidirectional"))
      (node (ref "U8") (pin "1") (pinfunction "OE_1") (pintype "input"))
      (node (ref "U8") (pin "10") (pinfunction "OE_10") (pintype "input"))
    )
    (net (code "54") (name "/V_SENSE") (class "Default")
      (node (ref "R27") (pin "1") (pinfunction "1_1") (pintype "passive"))
      (node (ref "R28") (pin "2") (pinfunction "2_2") (pintype "passive"))
      (node (ref "U1") (pin "15") (pinfunction "PC0/ADC123_IN10(5T)_15") (pintype "bidirectional"))
    )
    (net (code "55") (name "GND") (class "Default")
      (node (ref "BOOT") (pin "2") (pinfunction "2_2") (pintype "passive"))
      (node (ref "C1") (pin "2") (pinfunction "2_2") (pintype "passive"))
      (node (ref "C10") (pin "2") (pinfunction "2_2") (pintype "passive"))
      (node (ref "C11") (pin "2") (pinfunction "2_2") (pintype "passive"))
      (node (ref "C12") (pin "2") (pinfunction "2_2") (pintype "passive"))
      (node (ref "C13") (pin "2") (pinfunction "2_2") (pintype "passive"))
      (node (ref "C14") (pin "2") (pinfunction "2_2") (pintype "passive"))
      (node (ref "C15") (pin "2") (pinfunction "2_2") (pintype "passive"))
      (node (ref "C16") (pin "2") (pinfunction "2_2") (pintype "passive"))
      (node (ref "C17") (pin "2") (pinfunction "2_2") (pintype "passive"))
      (node (ref "C18") (pin "2") (pinfunction "2_2") (pintype "passive"))
      (node (ref "C19") (pin "2") (pinfunction "2_2") (pintype "passive"))
      (node (ref "C2") (pin "2") (pinfunction "2_2") (pintype "passive"))
      (node (ref "C20") (pin "2") (pinfunction "2_2") (pintype "passive"))
      (node (ref "C21") (pin "2") (pinfunction "2_2") (pintype "passive"))
      (node (ref "C22") (pin "2") (pinfunction "2_2") (pintype "passive"))
      (node (ref "C23") (pin "2") (pinfunction "2_2") (pintype "passive"))
      (node (ref "C24") (pin "2") (pinfunction "2_2") (pintype "passive"))
      (node (ref "C25") (pin "2") (pinfunction "2_2") (pintype "passive"))
      (node (ref "C26") (pin "2") (pinfunction "2_2") (pintype "passive"))
      (node (ref "C27") (pin "2") (pinfunction "2_2") (pintype "passive"))
      (node (ref "C28") (pin "2") (pinfunction "2_2") (pintype "passive"))
      (node (ref "C29") (pin "2") (pinfunction "2_2") (pintype "passive"))
      (node (ref "C3") (pin "2") (pinfunction "2_2") (pintype "passive"))
      (node (ref "C30") (pin "2") (pinfunction "2_2") (pintype "passive"))
      (node (ref "C31") (pin "2") (pinfunction "2_2") (pintype "passive"))
      (node (ref "C32") (pin "2") (pinfunction "2_2") (pintype "passive"))
      (node (ref "C33") (pin "2") (pinfunction "2_2") (pintype "passive"))
      (node (ref "C34") (pin "2") (pinfunction "2_2") (pintype "passive"))
      (node (ref "C35") (pin "2") (pinfunction "2_2") (pintype "passive"))
      (node (ref "C36") (pin "2") (pinfunction "2_2") (pintype "passive"))
      (node (ref "C37") (pin "2") (pinfunction "2_2") (pintype "passive"))
      (node (ref "C38") (pin "2") (pinfunction "2_2") (pintype "passive"))
      (node (ref "C39") (pin "2") (pinfunction "2_2") (pintype "passive"))
      (node (ref "C4") (pin "2") (pinfunction "2_2") (pintype "passive"))
      (node (ref "C40") (pin "2") (pinfunction "2_2") (pintype "passive"))
      (node (ref "C41") (pin "-") (pinfunction "-_-") (pintype "passive"))
      (node (ref "C5") (pin "2") (pinfunction "2_2") (pintype "passive"))
      (node (ref "C6") (pin "2") (pinfunction "2_2") (pintype "passive"))
      (node (ref "C7") (pin "2") (pinfunction "2_2") (pintype "passive"))
      (node (ref "C8") (pin "2") (pinfunction "2_2") (pintype "passive"))
      (node (ref "C9") (pin "2") (pinfunction "2_2") (pintype "passive"))
      (node (ref "IMU") (pin "3") (pinfunction "GND_3") (pintype "bidirectional"))
      (node (ref "J1") (pin "10") (pinfunction "GND_10") (pintype "bidirectional"))
      (node (ref "J1") (pin "9") (pinfunction "GND_9") (pintype "bidirectional"))
      (node (ref "J1") (pin "A") (pinfunction "GND_A") (pintype "bidirectional"))
      (node (ref "J1") (pin "B") (pinfunction "GND_B") (pintype "bidirectional"))
      (node (ref "J2") (pin "1") (pinfunction "GND_1") (pintype "bidirectional"))
      (node (ref "J3") (pin "1") (pinfunction "GND_1") (pintype "bidirectional"))
      (node (ref "J4") (pin "1") (pinfunction "GND_1") (pintype "bidirectional"))
      (node (ref "J5") (pin "1") (pinfunction "GND_1") (pintype "bidirectional"))
      (node (ref "J6") (pin "1") (pinfunction "1_1") (pintype "bidirectional"))
      (node (ref "J7") (pin "1") (pinfunction "1_1") (pintype "bidirectional"))
      (node (ref "J8") (pin "1") (pinfunction "1_1") (pintype "bidirectional"))
      (node (ref "J9") (pin "1") (pinfunction "1_1") (pintype "bidirectional"))
      (node (ref "JTAG") (pin "3") (pinfunction "GND_3") (pintype "bidirectional"))
      (node (ref "JTAG") (pin "5") (pinfunction "GND_5") (pintype "bidirectional"))
      (node (ref "JTAG") (pin "9") (pinfunction "GND_9") (pintype "bidirectional"))
      (node (ref "MOTORS") (pin "GND1") (pinfunction "GND_GND1") (pintype "bidirectional"))
      (node (ref "MOTORS") (pin "GND2") (pinfunction "GND_GND2") (pintype "bidirectional"))
      (node (ref "R22") (pin "1") (pinfunction "1_1") (pintype "passive"))
      (node (ref "R24") (pin "1") (pinfunction "1_1") (pintype "passive"))
      (node (ref "R25") (pin "1") (pinfunction "1_1") (pintype "passive"))
      (node (ref "R26") (pin "1") (pinfunction "1_1") (pintype "passive"))
      (node (ref "R28") (pin "1") (pinfunction "1_1") (pintype "passive"))
      (node (ref "R32") (pin "1") (pinfunction "1_1") (pintype "passive"))
      (node (ref "U$3") (pin "P$1") (pinfunction "1_P$1") (pintype "bidirectional"))
      (node (ref "U$3") (pin "P$2") (pinfunction "P$2_P$2") (pintype "bidirectional"))
      (node (ref "U$3") (pin "P$3") (pinfunction "P$3_P$3") (pintype "bidirectional"))
      (node (ref "U$3") (pin "P$4") (pinfunction "P$4_P$4") (pintype "bidirectional"))
      (node (ref "U$3") (pin "P$5") (pinfunction "P$5_P$5") (pintype "bidirectional"))
      (node (ref "U$3") (pin "P$6") (pinfunction "P$6_P$6") (pintype "bidirectional"))
      (node (ref "U$3") (pin "P$7") (pinfunction "P$7_P$7") (pintype "bidirectional"))
      (node (ref "U$3") (pin "P$8") (pinfunction "P$8_P$8") (pintype "bidirectional"))
      (node (ref "U1") (pin "10") (pinfunction "VSS_1_10") (pintype "bidirectional"))
      (node (ref "U1") (pin "20") (pinfunction "VSSA_20") (pintype "bidirectional"))
      (node (ref "U1") (pin "27") (pinfunction "VSS_2_27") (pintype "bidirectional"))
      (node (ref "U1") (pin "74") (pinfunction "VSS_3_74") (pintype "bidirectional"))
      (node (ref "U1") (pin "99") (pinfunction "VSS_4_99") (pintype "bidirectional"))
      (node (ref "U2") (pin "15") (pinfunction "AGND_15") (pintype "bidirectional"))
      (node (ref "U2") (pin "19") (pinfunction "AGND_19") (pintype "bidirectional"))
      (node (ref "U2") (pin "35") (pinfunction "IOGND_35") (pintype "bidirectional"))
      (node (ref "U2") (pin "36") (pinfunction "DGND_36") (pintype "bidirectional"))
      (node (ref "U2") (pin "47") (pinfunction "IOGND_47") (pintype "bidirectional"))
      (node (ref "U3") (pin "P$2") (pinfunction "GND_P$2") (pintype "input"))
      (node (ref "U4") (pin "1") (pinfunction "GND_1") (pintype "input"))
      (node (ref "U5") (pin "5") (pinfunction "GND_5") (pintype "bidirectional"))
      (node (ref "U6") (pin "5") (pinfunction "GND_5") (pintype "bidirectional"))
      (node (ref "U7") (pin "5") (pinfunction "GND_5") (pintype "power_in"))
      (node (ref "U8") (pin "7") (pinfunction "GND_7") (pintype "power_in"))
      (node (ref "U8") (pin "9") (pinfunction "I_9") (pintype "input"))
      (node (ref "X1") (pin "2") (pinfunction "G1_2") (pintype "bidirectional"))
      (node (ref "X1") (pin "4") (pinfunction "G2_4") (pintype "bidirectional"))
      (node (ref "X2") (pin "2") (pinfunction "GND_2") (pintype "power_in"))
    )
    (net (code "56") (name "Net-(ACT-PadC)") (class "Default")
      (node (ref "ACT") (pin "C") (pinfunction "C_C") (pintype "passive"))
      (node (ref "R24") (pin "2") (pinfunction "2_2") (pintype "passive"))
    )
    (net (code "57") (name "Net-(ERR-PadC)") (class "Default")
      (node (ref "ERR") (pin "C") (pinfunction "C_C") (pintype "passive"))
      (node (ref "R25") (pin "2") (pinfunction "2_2") (pintype "passive"))
    )
    (net (code "58") (name "Net-(J1-GREEN_A)") (class "Default")
      (node (ref "J1") (pin "12") (pinfunction "GREEN_A_12") (pintype "bidirectional"))
      (node (ref "R19") (pin "1") (pinfunction "1_1") (pintype "passive"))
    )
    (net (code "59") (name "Net-(J1-GREEN_K)") (class "Default")
      (node (ref "J1") (pin "11") (pinfunction "GREEN_K_11") (pintype "bidirectional"))
      (node (ref "U2") (pin "26") (pinfunction "LED_ACT/AN_EN_26") (pintype "bidirectional"))
    )
    (net (code "60") (name "Net-(J1-RX+)") (class "Default")
      (node (ref "J1") (pin "7") (pinfunction "RX+_7") (pintype "bidirectional"))
      (node (ref "R16") (pin "2") (pinfunction "2_2") (pintype "passive"))
      (node (ref "U2") (pin "14") (pinfunction "RD+_14") (pintype "bidirectional"))
    )
    (net (code "61") (name "Net-(J1-RX-)") (class "Default")
      (node (ref "J1") (pin "8") (pinfunction "RX-_8") (pintype "bidirectional"))
      (node (ref "R17") (pin "1") (pinfunction "1_1") (pintype "passive"))
      (node (ref "U2") (pin "13") (pinfunction "RD-_13") (pintype "bidirectional"))
    )
    (net (code "62") (name "Net-(J1-TX+)") (class "Default")
      (node (ref "J1") (pin "3") (pinfunction "TX+_3") (pintype "bidirectional"))
      (node (ref "R14") (pin "2") (pinfunction "2_2") (pintype "passive"))
      (node (ref "U2") (pin "17") (pinfunction "TD+_17") (pintype "bidirectional"))
    )
    (net (code "63") (name "Net-(J1-TX-)") (class "Default")
      (node (ref "J1") (pin "4") (pinfunction "TX-_4") (pintype "bidirectional"))
      (node (ref "R15") (pin "1") (pinfunction "1_1") (pintype "passive"))
      (node (ref "U2") (pin "16") (pinfunction "TD-_16") (pintype "bidirectional"))
    )
    (net (code "64") (name "Net-(J1-YELLOW_A)") (class "Default")
      (node (ref "J1") (pin "1") (pinfunction "YELLOW_A_1") (pintype "bidirectional"))
      (node (ref "R20") (pin "1") (pinfunction "1_1") (pintype "passive"))
    )
    (net (code "65") (name "Net-(J1-YELLOW_K)") (class "Default")
      (node (ref "J1") (pin "2") (pinfunction "YELLOW_K_2") (pintype "bidirectional"))
      (node (ref "U2") (pin "27") (pinfunction "LED_SPEED/AN_1_27") (pintype "bidirectional"))
    )
    (net (code "66") (name "Net-(J2-RX{slash}TX)") (class "Default")
      (node (ref "J2") (pin "3") (pinfunction "RX/TX_3") (pintype "bidirectional"))
      (node (ref "J3") (pin "3") (pinfunction "RX/TX_3") (pintype "bidirectional"))
      (node (ref "R8") (pin "2") (pinfunction "2_2") (pintype "passive"))
    )
    (net (code "67") (name "Net-(J2-VCC)") (class "Default")
      (node (ref "J2") (pin "2") (pinfunction "VCC_2") (pintype "bidirectional"))
      (node (ref "J3") (pin "2") (pinfunction "VCC_2") (pintype "bidirectional"))
      (node (ref "J4") (pin "2") (pinfunction "VCC_2") (pintype "bidirectional"))
      (node (ref "J5") (pin "2") (pinfunction "VCC_2") (pintype "bidirectional"))
      (node (ref "U6") (pin "3") (pinfunction "IP-1_3") (pintype "bidirectional"))
      (node (ref "U6") (pin "4") (pinfunction "IP-2_4") (pintype "bidirectional"))
    )
    (net (code "68") (name "Net-(J4-D+)") (class "Default")
      (node (ref "J4") (pin "3") (pinfunction "D+_3") (pintype "bidirectional"))
      (node (ref "J5") (pin "3") (pinfunction "D+_3") (pintype "bidirectional"))
      (node (ref "R30") (pin "1") (pinfunction "1_1") (pintype "passive"))
      (node (ref "R31") (pin "1") (pinfunction "1_1") (pintype "passive"))
      (node (ref "U7") (pin "6") (pinfunction "A_6") (pintype "passive"))
    )
    (net (code "69") (name "Net-(J4-D-)") (class "Default")
      (node (ref "J4") (pin "4") (pinfunction "D-_4") (pintype "bidirectional"))
      (node (ref "J5") (pin "4") (pinfunction "D-_4") (pintype "bidirectional"))
      (node (ref "R30") (pin "2") (pinfunction "2_2") (pintype "passive"))
      (node (ref "R32") (pin "2") (pinfunction "2_2") (pintype "passive"))
      (node (ref "U7") (pin "7") (pinfunction "B_7") (pintype "passive"))
    )
    (net (code "70") (name "Net-(J8-Pad3)") (class "Default")
      (node (ref "J8") (pin "3") (pinfunction "3_3") (pintype "bidirectional"))
      (node (ref "R10") (pin "1") (pinfunction "1_1") (pintype "passive"))
      (node (ref "R2") (pin "2") (pinfunction "2_2") (pintype "passive"))
    )
    (net (code "71") (name "Net-(J8-Pad4)") (class "Default")
      (node (ref "J8") (pin "4") (pinfunction "4_4") (pintype "bidirectional"))
      (node (ref "R1") (pin "2") (pinfunction "2_2") (pintype "passive"))
      (node (ref "R11") (pin "1") (pinfunction "1_1") (pintype "passive"))
    )
    (net (code "72") (name "Net-(J9-Pad3)") (class "Default")
      (node (ref "J9") (pin "3") (pinfunction "3_3") (pintype "bidirectional"))
      (node (ref "R12") (pin "1") (pinfunction "1_1") (pintype "passive"))
      (node (ref "R4") (pin "2") (pinfunction "2_2") (pintype "passive"))
    )
    (net (code "73") (name "Net-(J9-Pad4)") (class "Default")
      (node (ref "J9") (pin "4") (pinfunction "4_4") (pintype "bidirectional"))
      (node (ref "R13") (pin "1") (pinfunction "1_1") (pintype "passive"))
      (node (ref "R3") (pin "2") (pinfunction "2_2") (pintype "passive"))
    )
    (net (code "74") (name "Net-(PWR-PadC)") (class "Default")
      (node (ref "PWR") (pin "C") (pinfunction "C_C") (pintype "passive"))
      (node (ref "R26") (pin "2") (pinfunction "2_2") (pintype "passive"))
    )
    (net (code "75") (name "Net-(T1-1)") (class "Default")
      (node (ref "T1") (pin "T") (pinfunction "1_T") (pintype "bidirectional"))
      (node (ref "U1") (pin "96") (pinfunction "PB9/TIM11_CH1(5T)_96") (pintype "bidirectional"))
    )
    (net (code "76") (name "Net-(T2-1)") (class "Default")
      (node (ref "T2") (pin "T") (pinfunction "1_T") (pintype "bidirectional"))
      (node (ref "U1") (pin "95") (pinfunction "PB8/TIM10_CH1(5T)_95") (pintype "bidirectional"))
    )
    (net (code "77") (name "Net-(T3-1)") (class "Default")
      (node (ref "T3") (pin "T") (pinfunction "1_T") (pintype "bidirectional"))
      (node (ref "U1") (pin "80") (pinfunction "PC12/UART5_TX(5T)_80") (pintype "bidirectional"))
    )
    (net (code "78") (name "Net-(T4-1)") (class "Default")
      (node (ref "T4") (pin "T") (pinfunction "1_T") (pintype "bidirectional"))
      (node (ref "U1") (pin "81") (pinfunction "PD0/CAN1_RX(5T)_81") (pintype "bidirectional"))
    )
    (net (code "79") (name "Net-(T5-1)") (class "Default")
      (node (ref "T5") (pin "T") (pinfunction "1_T") (pintype "bidirectional"))
      (node (ref "U1") (pin "82") (pinfunction "PD1/CAN1_TX(5T)_82") (pintype "bidirectional"))
    )
    (net (code "80") (name "Net-(T6-1)") (class "Default")
      (node (ref "T6") (pin "T") (pinfunction "1_T") (pintype "bidirectional"))
      (node (ref "U1") (pin "83") (pinfunction "PD2/UART5_RX(5T)_83") (pintype "bidirectional"))
    )
    (net (code "81") (name "Net-(T7-1)") (class "Default")
      (node (ref "T7") (pin "T") (pinfunction "1_T") (pintype "bidirectional"))
      (node (ref "U1") (pin "97") (pinfunction "PE0(5T)_97") (pintype "bidirectional"))
    )
    (net (code "82") (name "Net-(T8-1)") (class "Default")
      (node (ref "T8") (pin "T") (pinfunction "1_T") (pintype "bidirectional"))
      (node (ref "U1") (pin "98") (pinfunction "PE1(5T)_98") (pintype "bidirectional"))
    )
    (net (code "83") (name "Net-(T9-1)") (class "Default")
      (node (ref "T9") (pin "T") (pinfunction "1_T") (pintype "bidirectional"))
      (node (ref "U1") (pin "3") (pinfunction "PE4(5T)_3") (pintype "bidirectional"))
    )
    (net (code "84") (name "Net-(T11-1)") (class "Default")
      (node (ref "C40") (pin "1") (pinfunction "1_1") (pintype "passive"))
      (node (ref "T11") (pin "T") (pinfunction "1_T") (pintype "bidirectional"))
      (node (ref "U1") (pin "12") (pinfunction "PH0-OSC_IN(5T)_12") (pintype "bidirectional"))
      (node (ref "X1") (pin "3") (pinfunction "P$2_3") (pintype "bidirectional"))
    )
    (net (code "85") (name "Net-(T18-1)") (class "Default")
      (node (ref "T18") (pin "T") (pinfunction "1_T") (pintype "bidirectional"))
      (node (ref "U1") (pin "67") (pinfunction "PA8/MCO1(5T)_67") (pintype "bidirectional"))
    )
    (net (code "86") (name "Net-(U1-PH1-OSC_OUT(5T))") (class "Default")
      (node (ref "C39") (pin "1") (pinfunction "1_1") (pintype "passive"))
      (node (ref "U1") (pin "13") (pinfunction "PH1-OSC_OUT(5T)_13") (pintype "bidirectional"))
      (node (ref "X1") (pin "1") (pinfunction "P$1_1") (pintype "bidirectional"))
    )
    (net (code "87") (name "Net-(U1-VCAP1)") (class "Default")
      (node (ref "C1") (pin "1") (pinfunction "1_1") (pintype "passive"))
      (node (ref "U1") (pin "49") (pinfunction "VCAP1_49") (pintype "bidirectional"))
    )
    (net (code "88") (name "Net-(U1-VCAP2)") (class "Default")
      (node (ref "C2") (pin "1") (pinfunction "1_1") (pintype "passive"))
      (node (ref "U1") (pin "73") (pinfunction "VCAP2_73") (pintype "bidirectional"))
    )
    (net (code "89") (name "Net-(U2-PFBIN1)") (class "Default")
      (node (ref "C33") (pin "1") (pinfunction "1_1") (pintype "passive"))
      (node (ref "C36") (pin "1") (pinfunction "1_1") (pintype "passive"))
      (node (ref "C37") (pin "1") (pinfunction "1_1") (pintype "passive"))
      (node (ref "C38") (pin "1") (pinfunction "1_1") (pintype "passive"))
      (node (ref "U2") (pin "18") (pinfunction "PFBIN1_18") (pintype "bidirectional"))
      (node (ref "U2") (pin "23") (pinfunction "PFBOUT_23") (pintype "bidirectional"))
      (node (ref "U2") (pin "37") (pinfunction "PFBIN2_37") (pintype "bidirectional"))
    )
    (net (code "90") (name "Net-(U2-RBIAS)") (class "Default")
      (node (ref "R22") (pin "2") (pinfunction "2_2") (pintype "passive"))
      (node (ref "U2") (pin "24") (pinfunction "RBIAS_24") (pintype "bidirectional"))
    )
    (net (code "91") (name "Net-(U2-RESERVED)") (class "Default")
      (node (ref "R18") (pin "2") (pinfunction "2_2") (pintype "passive"))
      (node (ref "U2") (pin "20") (pinfunction "RESERVED_20") (pintype "bidirectional"))
    )
    (net (code "92") (name "Net-(U2-RX_DV{slash}MII_MODE)") (class "Default")
      (node (ref "R23") (pin "1") (pinfunction "1_1") (pintype "passive"))
      (node (ref "U2") (pin "39") (pinfunction "RX_DV/MII_MODE_39") (pintype "bidirectional"))
    )
    (net (code "93") (name "Net-(U2-SW_STRAP#)") (class "Default")
      (node (ref "R21") (pin "1") (pinfunction "1_1") (pintype "passive"))
      (node (ref "U2") (pin "21") (pinfunction "SW_STRAP#_21") (pintype "bidirectional"))
    )
    (net (code "94") (name "Net-(U3-IN)") (class "Default")
      (node (ref "C41") (pin "+") (pinfunction "+_+") (pintype "passive"))
      (node (ref "J10") (pin "B") (pinfunction "B_B") (pintype "bidirectional"))
      (node (ref "J6") (pin "3") (pinfunction "3_3") (pintype "bidirectional"))
      (node (ref "U3") (pin "P$1") (pinfunction "IN_P$1") (pintype "input"))
    )
    (net (code "95") (name "Net-(U8A-O)") (class "Default")
      (node (ref "R7") (pin "1") (pinfunction "1_1") (pintype "passive"))
      (node (ref "R8") (pin "1") (pinfunction "1_1") (pintype "passive"))
      (node (ref "U8") (pin "3") (pinfunction "O_3") (pintype "output"))
      (node (ref "U8") (pin "5") (pinfunction "I_5") (pintype "input"))
    )
    (net (code "96") (name "Net-(U8B-OE)") (class "Default")
      (node (ref "R6") (pin "1") (pinfunction "1_1") (pintype "passive"))
      (node (ref "U8") (pin "4") (pinfunction "OE_4") (pintype "input"))
      (node (ref "U8") (pin "8") (pinfunction "O_8") (pintype "output"))
    )
    (net (code "97") (name "VCC") (class "Default")
      (node (ref "C10") (pin "1") (pinfunction "1_1") (pintype "passive"))
      (node (ref "C11") (pin "1") (pinfunction "1_1") (pintype "passive"))
      (node (ref "C12") (pin "1") (pinfunction "1_1") (pintype "passive"))
      (node (ref "C15") (pin "1") (pinfunction "1_1") (pintype "passive"))
      (node (ref "C16") (pin "1") (pinfunction "1_1") (pintype "passive"))
      (node (ref "C19") (pin "1") (pinfunction "1_1") (pintype "passive"))
      (node (ref "C20") (pin "1") (pinfunction "1_1") (pintype "passive"))
      (node (ref "C21") (pin "1") (pinfunction "1_1") (pintype "passive"))
      (node (ref "C22") (pin "1") (pinfunction "1_1") (pintype "passive"))
      (node (ref "C23") (pin "1") (pinfunction "1_1") (pintype "passive"))
      (node (ref "C24") (pin "1") (pinfunction "1_1") (pintype "passive"))
      (node (ref "C25") (pin "1") (pinfunction "1_1") (pintype "passive"))
      (node (ref "C26") (pin "1") (pinfunction "1_1") (pintype "passive"))
      (node (ref "C27") (pin "1") (pinfunction "1_1") (pintype "passive"))
      (node (ref "C28") (pin "1") (pinfunction "1_1") (pintype "passive"))
      (node (ref "C29") (pin "1") (pinfunction "1_1") (pintype "passive"))
      (node (ref "C3") (pin "1") (pinfunction "1_1") (pintype "passive"))
      (node (ref "C30") (pin "1") (pinfunction "1_1") (pintype "passive"))
      (node (ref "C31") (pin "1") (pinfunction "1_1") (pintype "passive"))
      (node (ref "C32") (pin "1") (pinfunction "1_1") (pintype "passive"))
      (node (ref "C35") (pin "1") (pinfunction "1_1") (pintype "passive"))
      (node (ref "C5") (pin "1") (pinfunction "1_1") (pintype "passive"))
      (node (ref "C6") (pin "1") (pinfunction "1_1") (pintype "passive"))
      (node (ref "C7") (pin "1") (pinfunction "1_1") (pintype "passive"))
      (node (ref "C8") (pin "1") (pinfunction "1_1") (pintype "passive"))
      (node (ref "C9") (pin "1") (pinfunction "1_1") (pintype "passive"))
      (node (ref "IMU") (pin "5") (pinfunction "3V3_5") (pintype "bidirectional"))
      (node (ref "J1") (pin "5") (pinfunction "CT_TX_5") (pintype "bidirectional"))
      (node (ref "J1") (pin "6") (pinfunction "CT_RX_6") (pintype "bidirectional"))
      (node (ref "JTAG") (pin "1") (pinfunction "VCC_1") (pintype "bidirectional"))
      (node (ref "PWR") (pin "A") (pinfunction "A_A") (pintype "passive"))
      (node (ref "R14") (pin "1") (pinfunction "1_1") (pintype "passive"))
      (node (ref "R15") (pin "2") (pinfunction "2_2") (pintype "passive"))
      (node (ref "R16") (pin "1") (pinfunction "1_1") (pintype "passive"))
      (node (ref "R17") (pin "2") (pinfunction "2_2") (pintype "passive"))
      (node (ref "R18") (pin "1") (pinfunction "1_1") (pintype "passive"))
      (node (ref "R19") (pin "2") (pinfunction "2_2") (pintype "passive"))
      (node (ref "R20") (pin "2") (pinfunction "2_2") (pintype "passive"))
      (node (ref "R21") (pin "2") (pinfunction "2_2") (pintype "passive"))
      (node (ref "R23") (pin "2") (pinfunction "2_2") (pintype "passive"))
      (node (ref "R29") (pin "2") (pinfunction "2_2") (pintype "passive"))
      (node (ref "R31") (pin "2") (pinfunction "2_2") (pintype "passive"))
      (node (ref "R9") (pin "2") (pinfunction "2_2") (pintype "passive"))
      (node (ref "U1") (pin "100") (pinfunction "VDD_6_100") (pintype "bidirectional"))
      (node (ref "U1") (pin "11") (pinfunction "VDD_1_11") (pintype "bidirectional"))
      (node (ref "U1") (pin "19") (pinfunction "VDD_2_19") (pintype "bidirectional"))
      (node (ref "U1") (pin "21") (pinfunction "VREF+_21") (pintype "bidirectional"))
      (node (ref "U1") (pin "22") (pinfunction "VDDA_22") (pintype "bidirectional"))
      (node (ref "U1") (pin "28") (pinfunction "VDD_3_28") (pintype "bidirectional"))
      (node (ref "U1") (pin "50") (pinfunction "VDD_4_50") (pintype "bidirectional"))
      (node (ref "U1") (pin "6") (pinfunction "VBAT_6") (pintype "bidirectional"))
      (node (ref "U1") (pin "75") (pinfunction "VDD_5_75") (pintype "bidirectional"))
      (node (ref "U2") (pin "22") (pinfunction "AVDD33_22") (pintype "bidirectional"))
      (node (ref "U2") (pin "32") (pinfunction "VDD_IO_32") (pintype "bidirectional"))
      (node (ref "U2") (pin "48") (pinfunction "VDD_IO_48") (pintype "bidirectional"))
      (node (ref "U4") (pin "4") (pinfunction "OUT_4") (pintype "passive"))
      (node (ref "U5") (pin "8") (pinfunction "VCC_8") (pintype "bidirectional"))
      (node (ref "U6") (pin "8") (pinfunction "VCC_8") (pintype "bidirectional"))
      (node (ref "U7") (pin "8") (pinfunction "VCC_8") (pintype "power_in"))
      (node (ref "X2") (pin "1") (pinfunction "OE_1") (pintype "input"))
      (node (ref "X2") (pin "4") (pinfunction "VCC_4") (pintype "power_in"))
    )
    (net (code "98") (name "unconnected-(IMU-VIN-Pad4)") (class "Default")
      (node (ref "IMU") (pin "4") (pinfunction "VIN_4") (pintype "bidirectional"))
    )
    (net (code "99") (name "unconnected-(U1-BOOT0-Pad94)") (class "Default")
      (node (ref "U1") (pin "94") (pinfunction "BOOT0_94") (pintype "bidirectional"))
    )
    (net (code "100") (name "unconnected-(U1-NRST-Pad14)") (class "Default")
      (node (ref "U1") (pin "14") (pinfunction "NRST_14") (pintype "bidirectional"))
    )
    (net (code "101") (name "unconnected-(U1-PA11{slash}USART1_CTS(5T)-Pad70)") (class "Default")
      (node (ref "U1") (pin "70") (pinfunction "PA11/USART1_CTS(5T)_70") (pintype "bidirectional"))
    )
    (net (code "102") (name "unconnected-(U1-PA12{slash}USART1_RTS(5T)-Pad71)") (class "Default")
      (node (ref "U1") (pin "71") (pinfunction "PA12/USART1_RTS(5T)_71") (pintype "bidirectional"))
    )
    (net (code "103") (name "unconnected-(U1-PB2{slash}BOOT1(5T)-Pad37)") (class "Default")
      (node (ref "U1") (pin "37") (pinfunction "PB2/BOOT1(5T)_37") (pintype "bidirectional"))
    )
    (net (code "104") (name "unconnected-(U1-PC9{slash}TIM3_CH4(5T)-Pad66)") (class "Default")
      (node (ref "U1") (pin "66") (pinfunction "PC9/TIM3_CH4(5T)_66") (pintype "bidirectional"))
    )
    (net (code "105") (name "unconnected-(U1-PC10{slash}UART4_TX(5T)-Pad78)") (class "Default")
      (node (ref "U1") (pin "78") (pinfunction "PC10/UART4_TX(5T)_78") (pintype "bidirectional"))
    )
    (net (code "106") (name "unconnected-(U1-PC13(5T)-Pad7)") (class "Default")
      (node (ref "U1") (pin "7") (pinfunction "PC13(5T)_7") (pintype "bidirectional"))
    )
    (net (code "107") (name "unconnected-(U1-PD3(5T)-Pad84)") (class "Default")
      (node (ref "U1") (pin "84") (pinfunction "PD3(5T)_84") (pintype "bidirectional"))
    )
    (net (code "108") (name "unconnected-(U1-PD4(5T)-Pad85)") (class "Default")
      (node (ref "U1") (pin "85") (pinfunction "PD4(5T)_85") (pintype "bidirectional"))
    )
    (net (code "109") (name "unconnected-(U1-PD8{slash}USART3_TX(5T)-Pad55)") (class "Default")
      (node (ref "U1") (pin "55") (pinfunction "PD8/USART3_TX(5T)_55") (pintype "bidirectional"))
    )
    (net (code "110") (name "unconnected-(U1-PD9{slash}USART3_RX(5T)-Pad56)") (class "Default")
      (node (ref "U1") (pin "56") (pinfunction "PD9/USART3_RX(5T)_56") (pintype "bidirectional"))
    )
    (net (code "111") (name "unconnected-(U1-PD10(5T)-Pad57)") (class "Default")
      (node (ref "U1") (pin "57") (pinfunction "PD10(5T)_57") (pintype "bidirectional"))
    )
    (net (code "112") (name "unconnected-(U1-PD11(5T)-Pad58)") (class "Default")
      (node (ref "U1") (pin "58") (pinfunction "PD11(5T)_58") (pintype "bidirectional"))
    )
    (net (code "113") (name "unconnected-(U1-PD14{slash}TIM4_CH3(5T)-Pad61)") (class "Default")
      (node (ref "U1") (pin "61") (pinfunction "PD14/TIM4_CH3(5T)_61") (pintype "bidirectional"))
    )
    (net (code "114") (name "unconnected-(U1-PE2{slash}ETH_MII_TXD3(5T)-Pad1)") (class "Default")
      (node (ref "U1") (pin "1") (pinfunction "PE2/ETH_MII_TXD3(5T)_1") (pintype "bidirectional"))
    )
    (net (code "115") (name "unconnected-(U1-PE3(5T)-Pad2)") (class "Default")
      (node (ref "U1") (pin "2") (pinfunction "PE3(5T)_2") (pintype "bidirectional"))
    )
    (net (code "116") (name "unconnected-(U1-PE12{slash}TIM1_CH3N(5T)-Pad43)") (class "Default")
      (node (ref "U1") (pin "43") (pinfunction "PE12/TIM1_CH3N(5T)_43") (pintype "bidirectional"))
    )
    (net (code "117") (name "unconnected-(U1-PE15{slash}TIM1_BKIN(5T)-Pad46)") (class "Default")
      (node (ref "U1") (pin "46") (pinfunction "PE15/TIM1_BKIN(5T)_46") (pintype "bidirectional"))
    )
    (net (code "118") (name "unconnected-(U2-CLKOUT-Pad25)") (class "Default")
      (node (ref "U2") (pin "25") (pinfunction "CLKOUT_25") (pintype "bidirectional"))
    )
    (net (code "119") (name "unconnected-(U2-COL{slash}PHYAD0-Pad42)") (class "Default")
      (node (ref "U2") (pin "42") (pinfunction "COL/PHYAD0_42") (pintype "bidirectional"))
    )
    (net (code "120") (name "unconnected-(U2-INT#{slash}PWDN#-Pad7)") (class "Default")
      (node (ref "U2") (pin "7") (pinfunction "INT#/PWDN#_7") (pintype "bidirectional"))
    )
    (net (code "121") (name "unconnected-(U2-JTAG_TCK-Pad8)") (class "Default")
      (node (ref "U2") (pin "8") (pinfunction "JTAG_TCK_8") (pintype "bidirectional"))
    )
    (net (code "122") (name "unconnected-(U2-JTAG_TDI-Pad12)") (class "Default")
      (node (ref "U2") (pin "12") (pinfunction "JTAG_TDI_12") (pintype "bidirectional"))
    )
    (net (code "123") (name "unconnected-(U2-JTAG_TDO-Pad9)") (class "Default")
      (node (ref "U2") (pin "9") (pinfunction "JTAG_TDO_9") (pintype "bidirectional"))
    )
    (net (code "124") (name "unconnected-(U2-JTAG_TMS-Pad10)") (class "Default")
      (node (ref "U2") (pin "10") (pinfunction "JTAG_TMS_10") (pintype "bidirectional"))
    )
    (net (code "125") (name "unconnected-(U2-JTAG_TRST#-Pad11)") (class "Default")
      (node (ref "U2") (pin "11") (pinfunction "JTAG_TRST#_11") (pintype "bidirectional"))
    )
    (net (code "126") (name "unconnected-(U2-LED_LINK{slash}AN_0-Pad28)") (class "Default")
      (node (ref "U2") (pin "28") (pinfunction "LED_LINK/AN_0_28") (pintype "bidirectional"))
    )
    (net (code "127") (name "unconnected-(U2-RXD2(MII){slash}PHYAD3-Pad45)") (class "Default")
      (node (ref "U2") (pin "45") (pinfunction "RXD2(MII)/PHYAD3_45") (pintype "bidirectional"))
    )
    (net (code "128") (name "unconnected-(U2-RXD3(MII){slash}PHYAD4-Pad46)") (class "Default")
      (node (ref "U2") (pin "46") (pinfunction "RXD3(MII)/PHYAD4_46") (pintype "bidirectional"))
    )
    (net (code "129") (name "unconnected-(U2-RX_CLK(MII)-Pad38)") (class "Default")
      (node (ref "U2") (pin "38") (pinfunction "RX_CLK(MII)_38") (pintype "bidirectional"))
    )
    (net (code "130") (name "unconnected-(U2-RX_ER{slash}AMDIX_EN-Pad41)") (class "Default")
      (node (ref "U2") (pin "41") (pinfunction "RX_ER/AMDIX_EN_41") (pintype "bidirectional"))
    )
    (net (code "131") (name "unconnected-(U2-TXD2(MII)-Pad5)") (class "Default")
      (node (ref "U2") (pin "5") (pinfunction "TXD2(MII)_5") (pintype "bidirectional"))
    )
    (net (code "132") (name "unconnected-(U2-TXD3(MII)-Pad6)") (class "Default")
      (node (ref "U2") (pin "6") (pinfunction "TXD3(MII)_6") (pintype "bidirectional"))
    )
    (net (code "133") (name "unconnected-(U2-TX_CLK(MII)-Pad1)") (class "Default")
      (node (ref "U2") (pin "1") (pinfunction "TX_CLK(MII)_1") (pintype "bidirectional"))
    )
    (net (code "134") (name "unconnected-(U2-XO-Pad33)") (class "Default")
      (node (ref "U2") (pin "33") (pinfunction "XO_33") (pintype "bidirectional"))
    )
    (net (code "135") (name "unconnected-(U5-FAULT#-Pad6)") (class "Default")
      (node (ref "U5") (pin "6") (pinfunction "FAULT#_6") (pintype "bidirectional"))
    )
    (net (code "136") (name "unconnected-(U6-FAULT#-Pad6)") (class "Default")
      (node (ref "U6") (pin "6") (pinfunction "FAULT#_6") (pintype "bidirectional"))
    )
  )
)
